# input.net
KiCad netlist of a schematic drawn in EAGLE
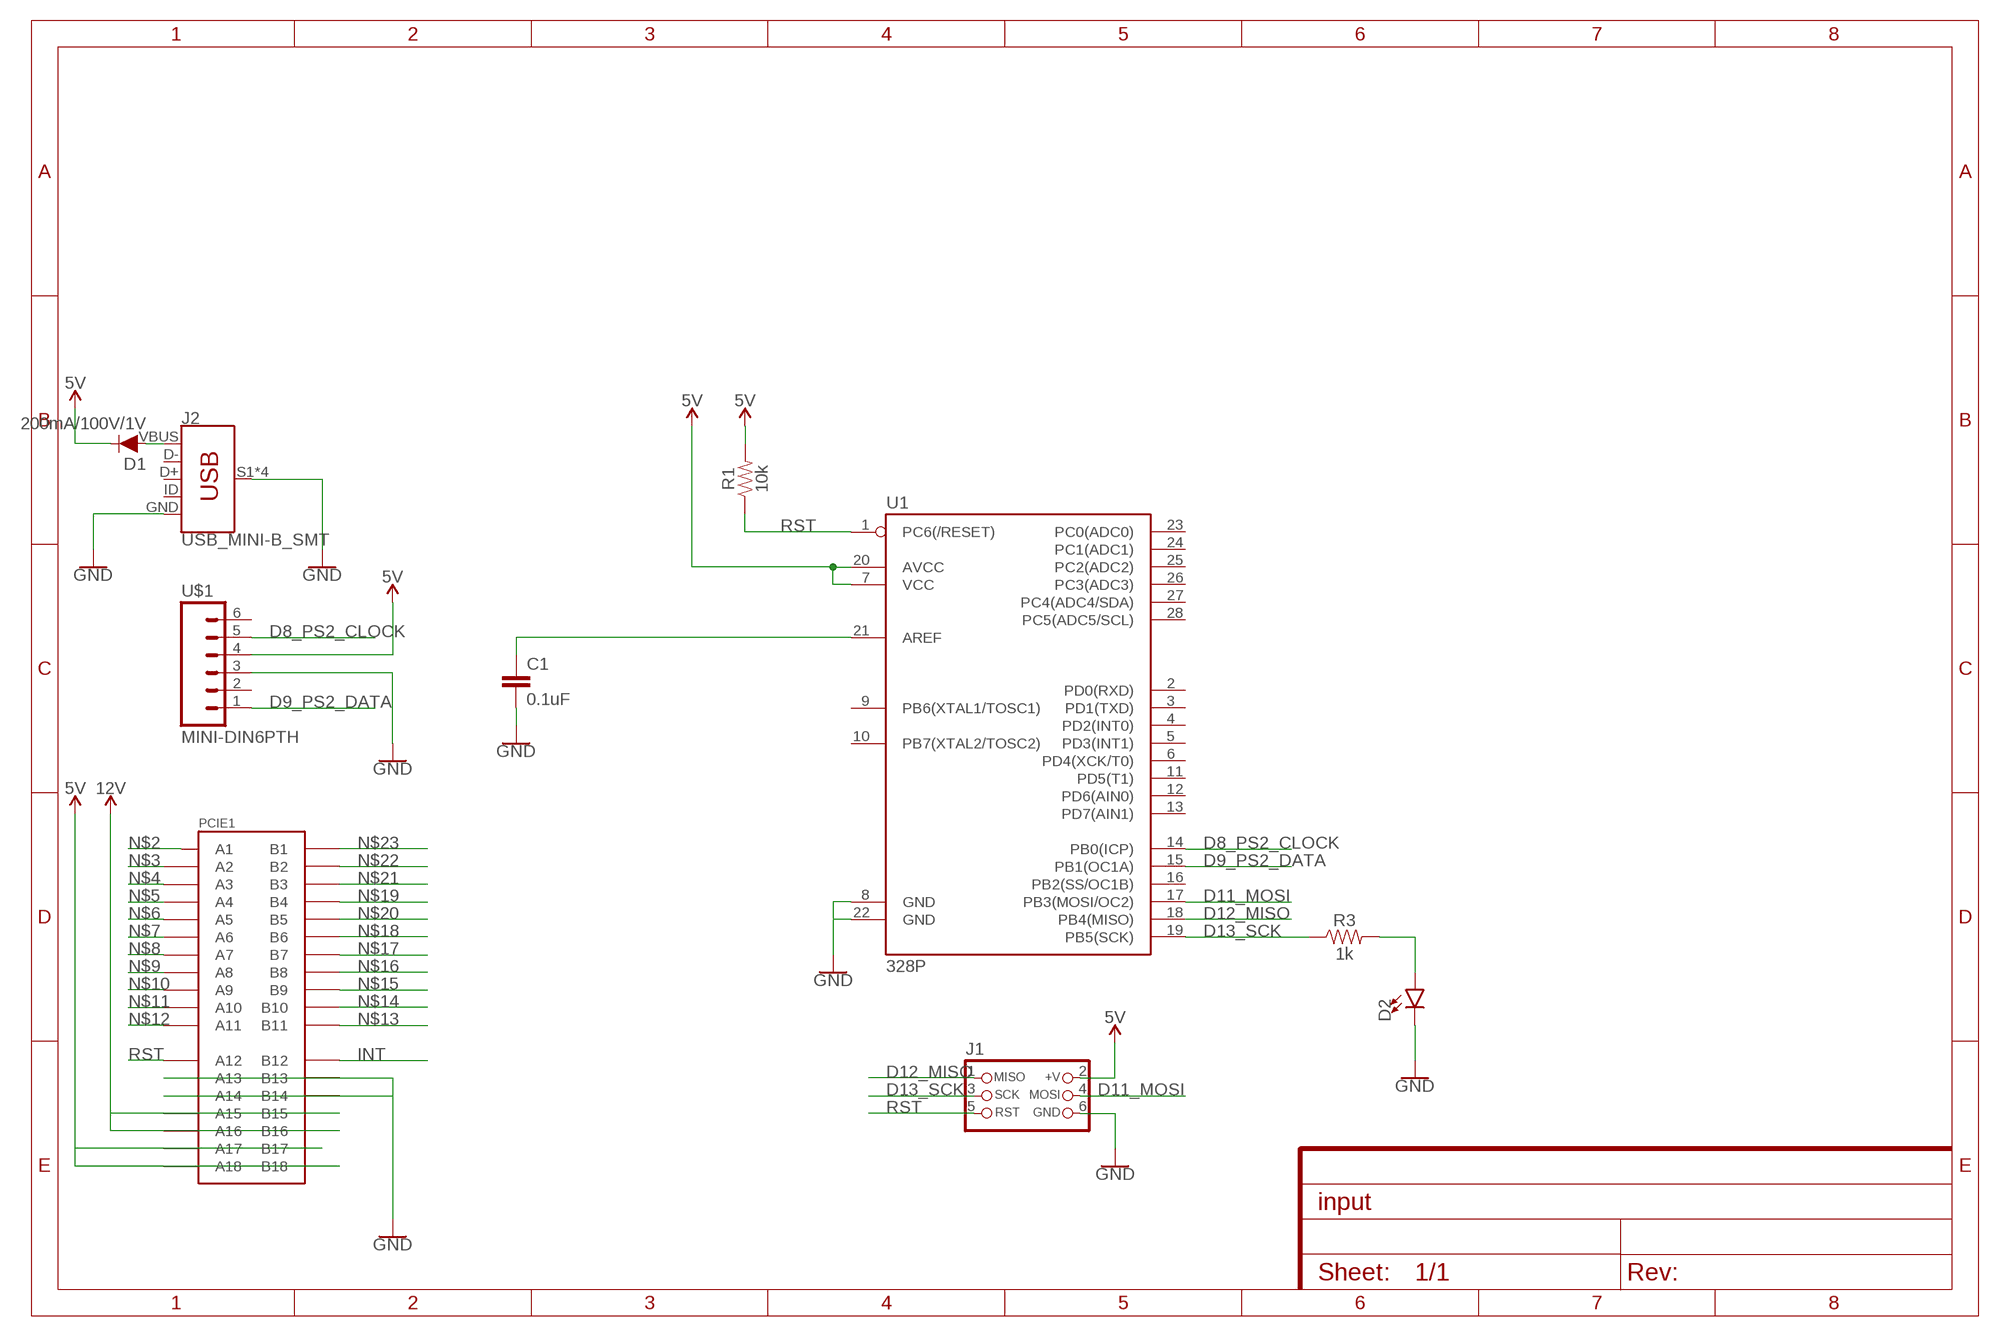
[diagram p0: schematic, sheet 1]

(export (version "E")
  (design (tool "Eeschema 10.0.6"))
  (components
    (comp (ref "C1")
      (value "0.1uF")
      (footprint "eagle-import:CAP-PTH-SMALL-KIT")
      (libsource (lib "eagle-import") (part "0.1UF-KIT-EZ-50V-20%"))
    )
    (comp (ref "D1")
      (value "200mA/100V/1V")
      (footprint "eagle-import:DIODE-1N4148")
      (libsource (lib "eagle-import") (part "DIODE-1N4148"))
    )
    (comp (ref "D2")
      (value "LED5MM-KIT")
      (footprint "eagle-import:LED_5MM-KIT")
      (libsource (lib "eagle-import") (part "LED5MM-KIT"))
    )
    (comp (ref "J1")
      (value "CON_HEADER_PRG_AVR_ICSP-PTH")
      (footprint "eagle-import:HEADER_PRG_2X03")
      (libsource (lib "eagle-import") (part "CON_HEADER_PRG_AVR_ICSP-PTH"))
    )
    (comp (ref "J2")
      (value "USB_MINI-B_SMT")
      (footprint "eagle-import:USB-MINIB")
      (libsource (lib "eagle-import") (part "USB_MINI-B_SMT"))
    )
    (comp (ref "PCIE1")
      (value "PCIE-36-EDGE")
      (footprint "eagle-import:PCIE-36-EDGE")
      (libsource (lib "eagle-import") (part "PCIE-36-EDGE"))
    )
    (comp (ref "R1")
      (value "10k")
      (footprint "eagle-import:AXIAL-0.3")
      (libsource (lib "eagle-import") (part "10KOHM-HORIZ-1/4W-5%"))
    )
    (comp (ref "R3")
      (value "1k")
      (footprint "eagle-import:AXIAL-0.3")
      (libsource (lib "eagle-import") (part "1KOHM-HORIZ-1/4W-5%"))
    )
    (comp (ref "U$1")
      (value "MINI-DIN6PTH")
      (footprint "eagle-import:MINI-DIN6")
      (libsource (lib "eagle-import") (part "MINI-DIN6PTH"))
    )
    (comp (ref "U1")
      (value "328P")
      (footprint "eagle-import:DIP28")
      (libsource (lib "eagle-import") (part "ATMEGA328P_PDIP"))
    )
  )
  (nets
    (net (code "1") (name "/D8_PS2_CLOCK") (class "Default")
      (node (ref "U$1") (pin "5") (pinfunction "5_5") (pintype "passive"))
      (node (ref "U1") (pin "14") (pinfunction "PB0(ICP)_14") (pintype "bidirectional"))
    )
    (net (code "2") (name "/D9_PS2_DATA") (class "Default")
      (node (ref "U$1") (pin "1") (pinfunction "1_1") (pintype "passive"))
      (node (ref "U1") (pin "15") (pinfunction "PB1(OC1A)_15") (pintype "bidirectional"))
    )
    (net (code "3") (name "/D11_MOSI") (class "Default")
      (node (ref "J1") (pin "4") (pinfunction "MOSI_4") (pintype "passive"))
      (node (ref "U1") (pin "17") (pinfunction "PB3(MOSI/OC2)_17") (pintype "bidirectional"))
    )
    (net (code "4") (name "/D12_MISO") (class "Default")
      (node (ref "J1") (pin "1") (pinfunction "MISO_1") (pintype "passive"))
      (node (ref "U1") (pin "18") (pinfunction "PB4(MISO)_18") (pintype "bidirectional"))
    )
    (net (code "5") (name "/D13_SCK") (class "Default")
      (node (ref "J1") (pin "3") (pinfunction "SCK_3") (pintype "passive"))
      (node (ref "R3") (pin "P$1") (pinfunction "1_P$1") (pintype "passive"))
      (node (ref "U1") (pin "19") (pinfunction "PB5(SCK)_19") (pintype "bidirectional"))
    )
    (net (code "6") (name "/INT") (class "Default")
      (node (ref "PCIE1") (pin "B12") (pinfunction "B12_B12") (pintype "bidirectional"))
    )
    (net (code "7") (name "/N$2") (class "Default")
      (node (ref "PCIE1") (pin "A1") (pinfunction "A1_A1") (pintype "bidirectional"))
    )
    (net (code "8") (name "/N$3") (class "Default")
      (node (ref "PCIE1") (pin "A2") (pinfunction "A2_A2") (pintype "bidirectional"))
    )
    (net (code "9") (name "/N$4") (class "Default")
      (node (ref "PCIE1") (pin "A3") (pinfunction "A3_A3") (pintype "bidirectional"))
    )
    (net (code "10") (name "/N$5") (class "Default")
      (node (ref "PCIE1") (pin "A4") (pinfunction "A4_A4") (pintype "bidirectional"))
    )
    (net (code "11") (name "/N$6") (class "Default")
      (node (ref "PCIE1") (pin "A5") (pinfunction "A5_A5") (pintype "bidirectional"))
    )
    (net (code "12") (name "/N$7") (class "Default")
      (node (ref "PCIE1") (pin "A6") (pinfunction "A6_A6") (pintype "bidirectional"))
    )
    (net (code "13") (name "/N$8") (class "Default")
      (node (ref "PCIE1") (pin "A7") (pinfunction "A7_A7") (pintype "bidirectional"))
    )
    (net (code "14") (name "/N$9") (class "Default")
      (node (ref "PCIE1") (pin "A8") (pinfunction "A8_A8") (pintype "bidirectional"))
    )
    (net (code "15") (name "/N$10") (class "Default")
      (node (ref "PCIE1") (pin "A9") (pinfunction "A9_A9") (pintype "bidirectional"))
    )
    (net (code "16") (name "/N$11") (class "Default")
      (node (ref "PCIE1") (pin "A10") (pinfunction "A10_A10") (pintype "bidirectional"))
    )
    (net (code "17") (name "/N$12") (class "Default")
      (node (ref "PCIE1") (pin "A11") (pinfunction "A11_A11") (pintype "bidirectional"))
    )
    (net (code "18") (name "/N$13") (class "Default")
      (node (ref "PCIE1") (pin "B11") (pinfunction "B11_B11") (pintype "bidirectional"))
    )
    (net (code "19") (name "/N$14") (class "Default")
      (node (ref "PCIE1") (pin "B10") (pinfunction "B10_B10") (pintype "bidirectional"))
    )
    (net (code "20") (name "/N$15") (class "Default")
      (node (ref "PCIE1") (pin "B9") (pinfunction "B9_B9") (pintype "bidirectional"))
    )
    (net (code "21") (name "/N$16") (class "Default")
      (node (ref "PCIE1") (pin "B8") (pinfunction "B8_B8") (pintype "bidirectional"))
    )
    (net (code "22") (name "/N$17") (class "Default")
      (node (ref "PCIE1") (pin "B7") (pinfunction "B7_B7") (pintype "bidirectional"))
    )
    (net (code "23") (name "/N$18") (class "Default")
      (node (ref "PCIE1") (pin "B6") (pinfunction "B6_B6") (pintype "bidirectional"))
    )
    (net (code "24") (name "/N$19") (class "Default")
      (node (ref "PCIE1") (pin "B4") (pinfunction "B4_B4") (pintype "bidirectional"))
    )
    (net (code "25") (name "/N$20") (class "Default")
      (node (ref "PCIE1") (pin "B5") (pinfunction "B5_B5") (pintype "bidirectional"))
    )
    (net (code "26") (name "/N$21") (class "Default")
      (node (ref "PCIE1") (pin "B3") (pinfunction "B3_B3") (pintype "bidirectional"))
    )
    (net (code "27") (name "/N$22") (class "Default")
      (node (ref "PCIE1") (pin "B2") (pinfunction "B2_B2") (pintype "bidirectional"))
    )
    (net (code "28") (name "/N$23") (class "Default")
      (node (ref "PCIE1") (pin "B1") (pinfunction "B1_B1") (pintype "bidirectional"))
    )
    (net (code "29") (name "/RST") (class "Default")
      (node (ref "J1") (pin "5") (pinfunction "RST_5") (pintype "passive"))
      (node (ref "PCIE1") (pin "A12") (pinfunction "A12_A12") (pintype "bidirectional"))
      (node (ref "R1") (pin "P$1") (pinfunction "1_P$1") (pintype "passive"))
      (node (ref "U1") (pin "1") (pinfunction "PC6(/RESET)_1") (pintype "bidirectional"))
    )
    (net (code "30") (name "5V") (class "Default")
      (node (ref "D1") (pin "C") (pinfunction "C_C") (pintype "passive"))
      (node (ref "J1") (pin "2") (pinfunction "+V_2") (pintype "passive"))
      (node (ref "PCIE1") (pin "A17") (pinfunction "A17_A17") (pintype "bidirectional"))
      (node (ref "PCIE1") (pin "A18") (pinfunction "A18_A18") (pintype "bidirectional"))
      (node (ref "PCIE1") (pin "B17") (pinfunction "B17_B17") (pintype "bidirectional"))
      (node (ref "PCIE1") (pin "B18") (pinfunction "B18_B18") (pintype "bidirectional"))
      (node (ref "R1") (pin "P$2") (pinfunction "2_P$2") (pintype "passive"))
      (node (ref "U$1") (pin "4") (pinfunction "4_4") (pintype "passive"))
      (node (ref "U1") (pin "20") (pinfunction "AVCC_20") (pintype "bidirectional"))
      (node (ref "U1") (pin "7") (pinfunction "VCC_7") (pintype "bidirectional"))
    )
    (net (code "31") (name "12V") (class "Default")
      (node (ref "PCIE1") (pin "A15") (pinfunction "A15_A15") (pintype "bidirectional"))
      (node (ref "PCIE1") (pin "A16") (pinfunction "A16_A16") (pintype "bidirectional"))
      (node (ref "PCIE1") (pin "B15") (pinfunction "B15_B15") (pintype "bidirectional"))
      (node (ref "PCIE1") (pin "B16") (pinfunction "B16_B16") (pintype "bidirectional"))
    )
    (net (code "32") (name "GND") (class "Default")
      (node (ref "C1") (pin "2") (pinfunction "2_2") (pintype "passive"))
      (node (ref "D2") (pin "K") (pinfunction "C_K") (pintype "passive"))
      (node (ref "J1") (pin "6") (pinfunction "GND_6") (pintype "passive"))
      (node (ref "J2") (pin "GND") (pinfunction "GND_GND") (pintype "power_in"))
      (node (ref "J2") (pin "S1") (pinfunction "SHIELD_S1") (pintype "bidirectional"))
      (node (ref "J2") (pin "S2") (pinfunction "SHIELD_S2") (pintype "bidirectional"))
      (node (ref "J2") (pin "S3") (pinfunction "SHIELD_S3") (pintype "bidirectional"))
      (node (ref "J2") (pin "S4") (pinfunction "SHIELD_S4") (pintype "bidirectional"))
      (node (ref "PCIE1") (pin "A13") (pinfunction "A13_A13") (pintype "bidirectional"))
      (node (ref "PCIE1") (pin "A14") (pinfunction "A14_A14") (pintype "bidirectional"))
      (node (ref "PCIE1") (pin "B13") (pinfunction "B13_B13") (pintype "bidirectional"))
      (node (ref "PCIE1") (pin "B14") (pinfunction "B14_B14") (pintype "bidirectional"))
      (node (ref "U$1") (pin "3") (pinfunction "3_3") (pintype "passive"))
      (node (ref "U1") (pin "22") (pinfunction "GND_22") (pintype "bidirectional"))
      (node (ref "U1") (pin "8") (pinfunction "GND_8") (pintype "bidirectional"))
    )
    (net (code "33") (name "Net-(D1-PadA)") (class "Default")
      (node (ref "D1") (pin "A") (pinfunction "A_A") (pintype "passive"))
      (node (ref "J2") (pin "VBUS") (pinfunction "VBUS_VBUS") (pintype "power_in"))
    )
    (net (code "34") (name "Net-(R3-2)") (class "Default")
      (node (ref "D2") (pin "A") (pinfunction "A_A") (pintype "passive"))
      (node (ref "R3") (pin "P$2") (pinfunction "2_P$2") (pintype "passive"))
    )
    (net (code "35") (name "Net-(U1-AREF)") (class "Default")
      (node (ref "C1") (pin "1") (pinfunction "1_1") (pintype "passive"))
      (node (ref "U1") (pin "21") (pinfunction "AREF_21") (pintype "bidirectional"))
    )
    (net (code "36") (name "unconnected-(J2-PadD+)") (class "Default")
      (node (ref "J2") (pin "D+") (pinfunction "D+_D+") (pintype "bidirectional"))
    )
    (net (code "37") (name "unconnected-(J2-PadD-)") (class "Default")
      (node (ref "J2") (pin "D-") (pinfunction "D-_D-") (pintype "bidirectional"))
    )
    (net (code "38") (name "unconnected-(J2-PadID)") (class "Default")
      (node (ref "J2") (pin "ID") (pinfunction "ID_ID") (pintype "bidirectional"))
    )
    (net (code "39") (name "unconnected-(U$1-Pad2)") (class "Default")
      (node (ref "U$1") (pin "2") (pinfunction "2_2") (pintype "passive"))
    )
    (net (code "40") (name "unconnected-(U$1-Pad6)") (class "Default")
      (node (ref "U$1") (pin "6") (pinfunction "6_6") (pintype "passive"))
    )
    (net (code "41") (name "unconnected-(U1-PB2(SS{slash}OC1B)-Pad16)") (class "Default")
      (node (ref "U1") (pin "16") (pinfunction "PB2(SS/OC1B)_16") (pintype "bidirectional"))
    )
    (net (code "42") (name "unconnected-(U1-PB6(XTAL1{slash}TOSC1)-Pad9)") (class "Default")
      (node (ref "U1") (pin "9") (pinfunction "PB6(XTAL1/TOSC1)_9") (pintype "bidirectional"))
    )
    (net (code "43") (name "unconnected-(U1-PB7(XTAL2{slash}TOSC2)-Pad10)") (class "Default")
      (node (ref "U1") (pin "10") (pinfunction "PB7(XTAL2/TOSC2)_10") (pintype "bidirectional"))
    )
    (net (code "44") (name "unconnected-(U1-PC0(ADC0)-Pad23)") (class "Default")
      (node (ref "U1") (pin "23") (pinfunction "PC0(ADC0)_23") (pintype "bidirectional"))
    )
    (net (code "45") (name "unconnected-(U1-PC1(ADC1)-Pad24)") (class "Default")
      (node (ref "U1") (pin "24") (pinfunction "PC1(ADC1)_24") (pintype "bidirectional"))
    )
    (net (code "46") (name "unconnected-(U1-PC2(ADC2)-Pad25)") (class "Default")
      (node (ref "U1") (pin "25") (pinfunction "PC2(ADC2)_25") (pintype "bidirectional"))
    )
    (net (code "47") (name "unconnected-(U1-PC3(ADC3)-Pad26)") (class "Default")
      (node (ref "U1") (pin "26") (pinfunction "PC3(ADC3)_26") (pintype "bidirectional"))
    )
    (net (code "48") (name "unconnected-(U1-PC4(ADC4{slash}SDA)-Pad27)") (class "Default")
      (node (ref "U1") (pin "27") (pinfunction "PC4(ADC4/SDA)_27") (pintype "bidirectional"))
    )
    (net (code "49") (name "unconnected-(U1-PC5(ADC5{slash}SCL)-Pad28)") (class "Default")
      (node (ref "U1") (pin "28") (pinfunction "PC5(ADC5/SCL)_28") (pintype "bidirectional"))
    )
    (net (code "50") (name "unconnected-(U1-PD0(RXD)-Pad2)") (class "Default")
      (node (ref "U1") (pin "2") (pinfunction "PD0(RXD)_2") (pintype "bidirectional"))
    )
    (net (code "51") (name "unconnected-(U1-PD1(TXD)-Pad3)") (class "Default")
      (node (ref "U1") (pin "3") (pinfunction "PD1(TXD)_3") (pintype "bidirectional"))
    )
    (net (code "52") (name "unconnected-(U1-PD2(INT0)-Pad4)") (class "Default")
      (node (ref "U1") (pin "4") (pinfunction "PD2(INT0)_4") (pintype "bidirectional"))
    )
    (net (code "53") (name "unconnected-(U1-PD3(INT1)-Pad5)") (class "Default")
      (node (ref "U1") (pin "5") (pinfunction "PD3(INT1)_5") (pintype "bidirectional"))
    )
    (net (code "54") (name "unconnected-(U1-PD4(XCK{slash}T0)-Pad6)") (class "Default")
      (node (ref "U1") (pin "6") (pinfunction "PD4(XCK/T0)_6") (pintype "bidirectional"))
    )
    (net (code "55") (name "unconnected-(U1-PD5(T1)-Pad11)") (class "Default")
      (node (ref "U1") (pin "11") (pinfunction "PD5(T1)_11") (pintype "bidirectional"))
    )
    (net (code "56") (name "unconnected-(U1-PD6(AIN0)-Pad12)") (class "Default")
      (node (ref "U1") (pin "12") (pinfunction "PD6(AIN0)_12") (pintype "bidirectional"))
    )
    (net (code "57") (name "unconnected-(U1-PD7(AIN1)-Pad13)") (class "Default")
      (node (ref "U1") (pin "13") (pinfunction "PD7(AIN1)_13") (pintype "bidirectional"))
    )
  )
)
